# VideoBoy1_12.net
KiCad netlist of a schematic drawn in EAGLE
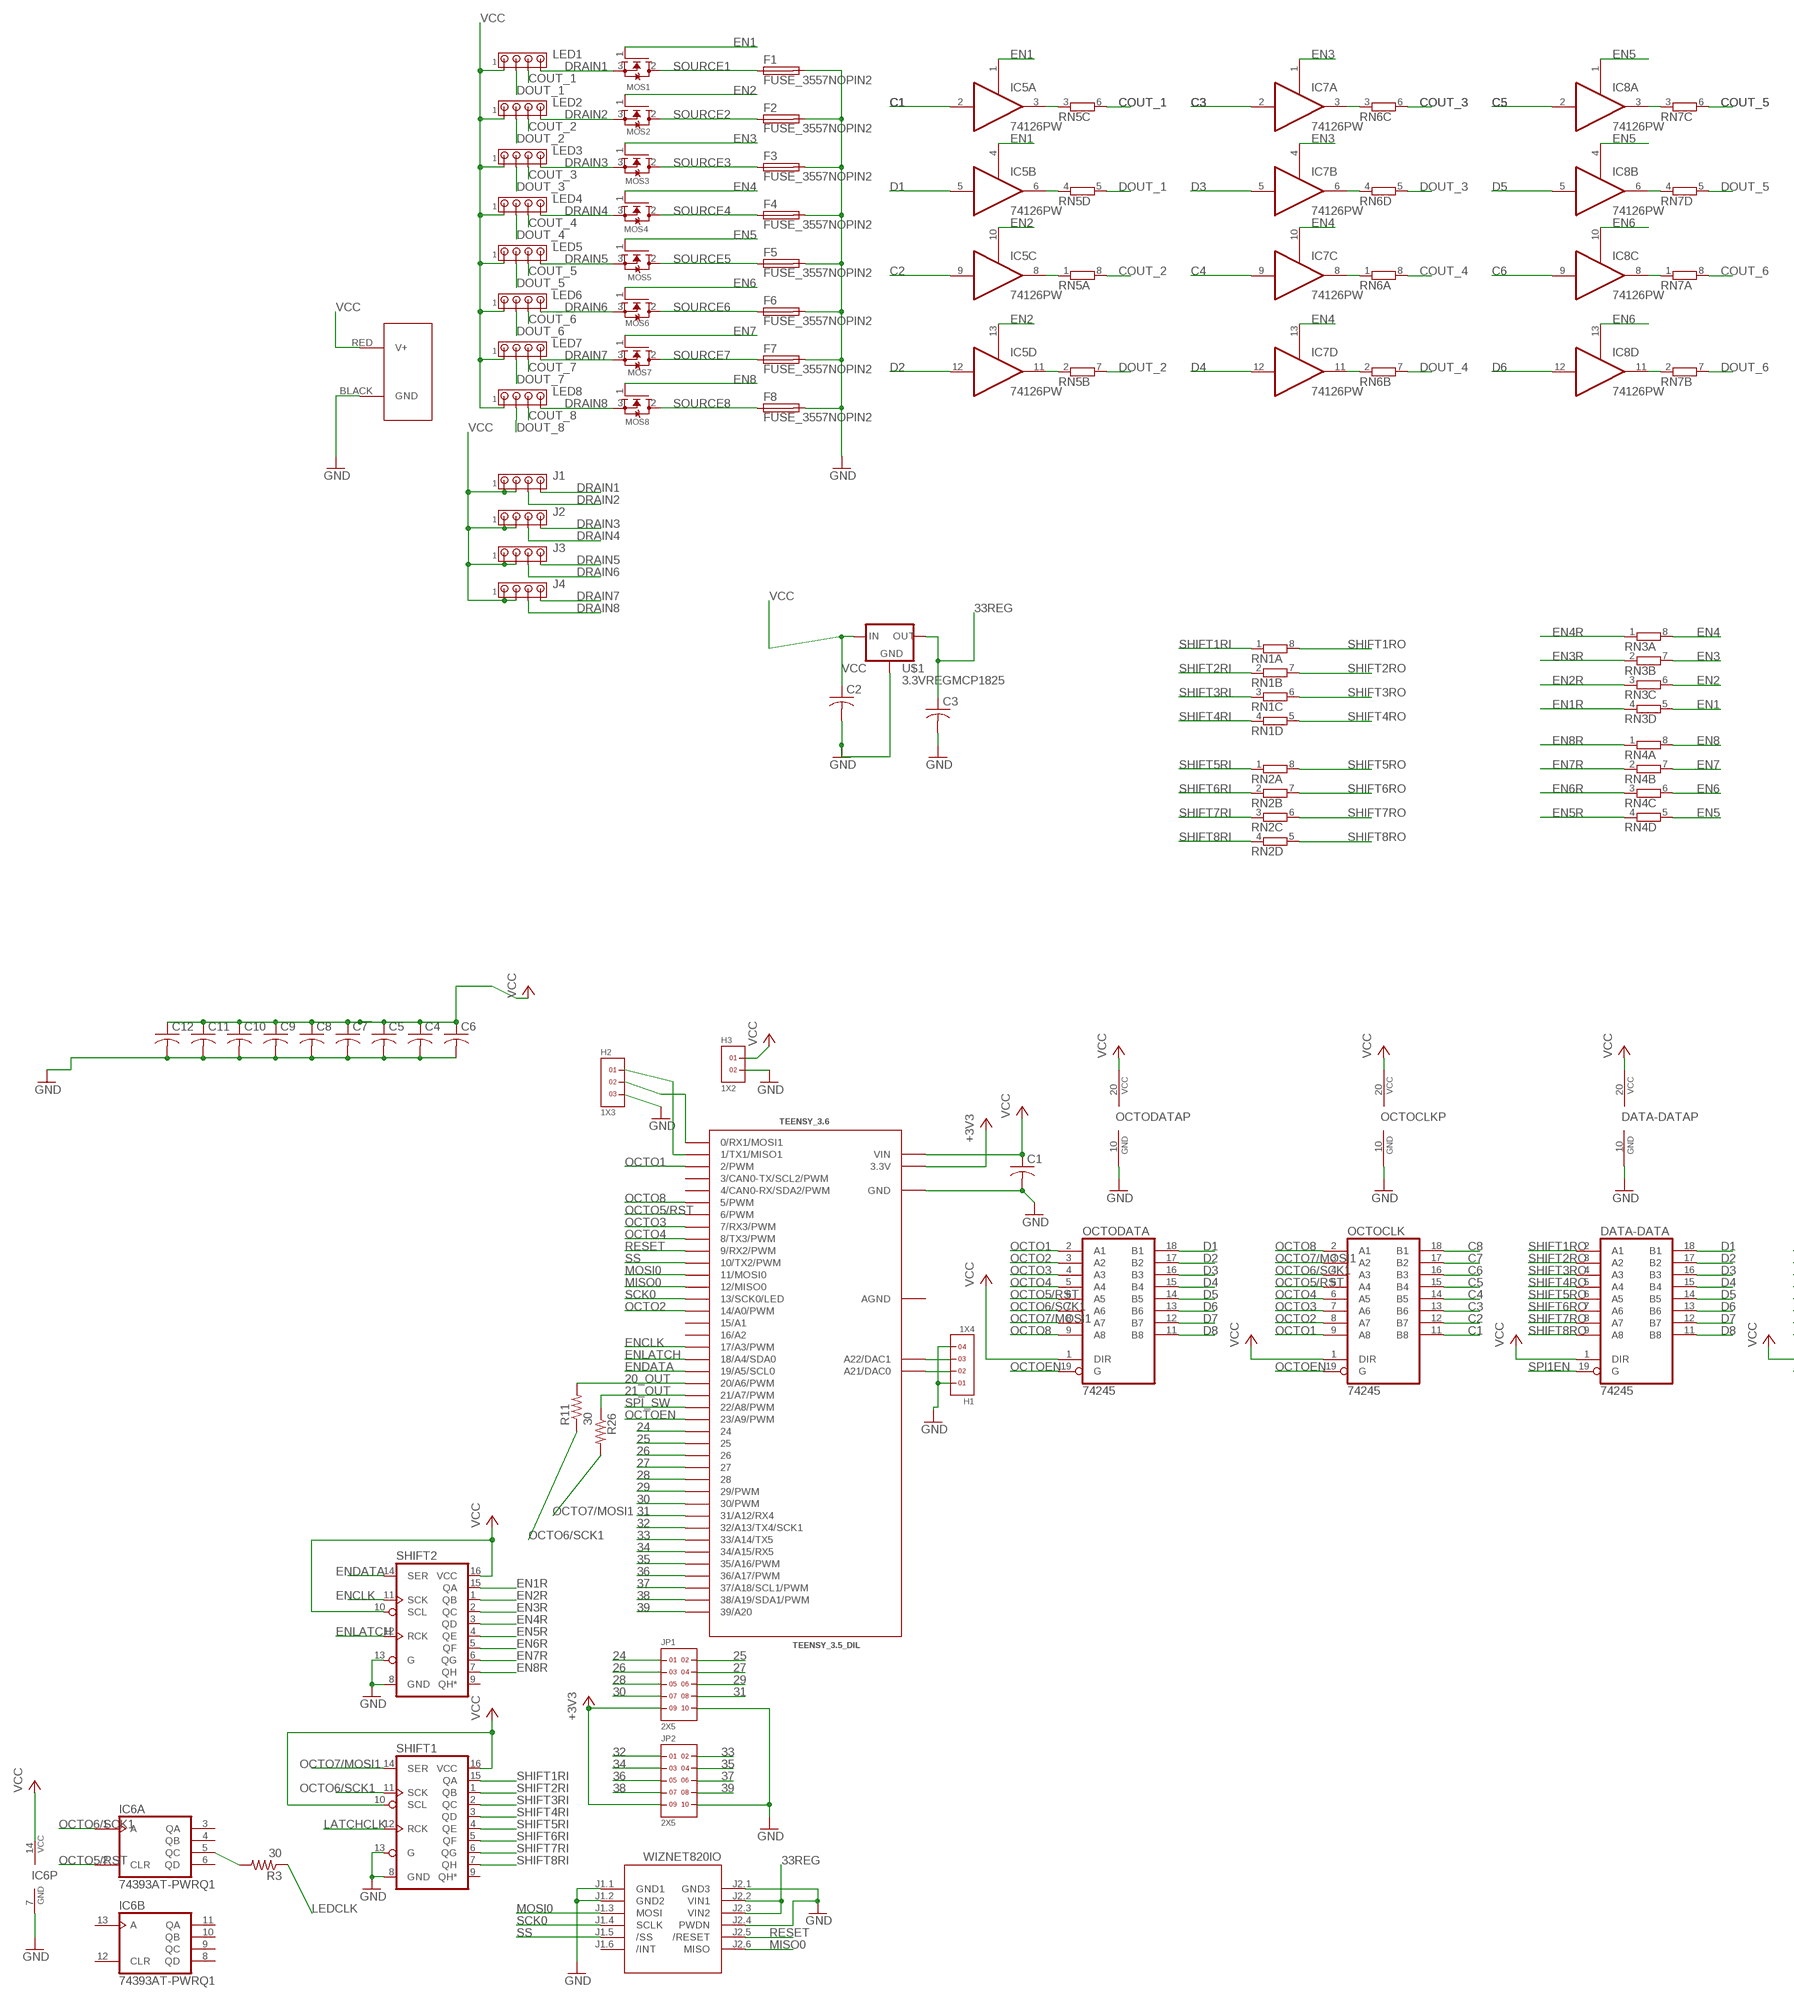
[diagram p0: schematic, sheet 1, part 1 of 2]
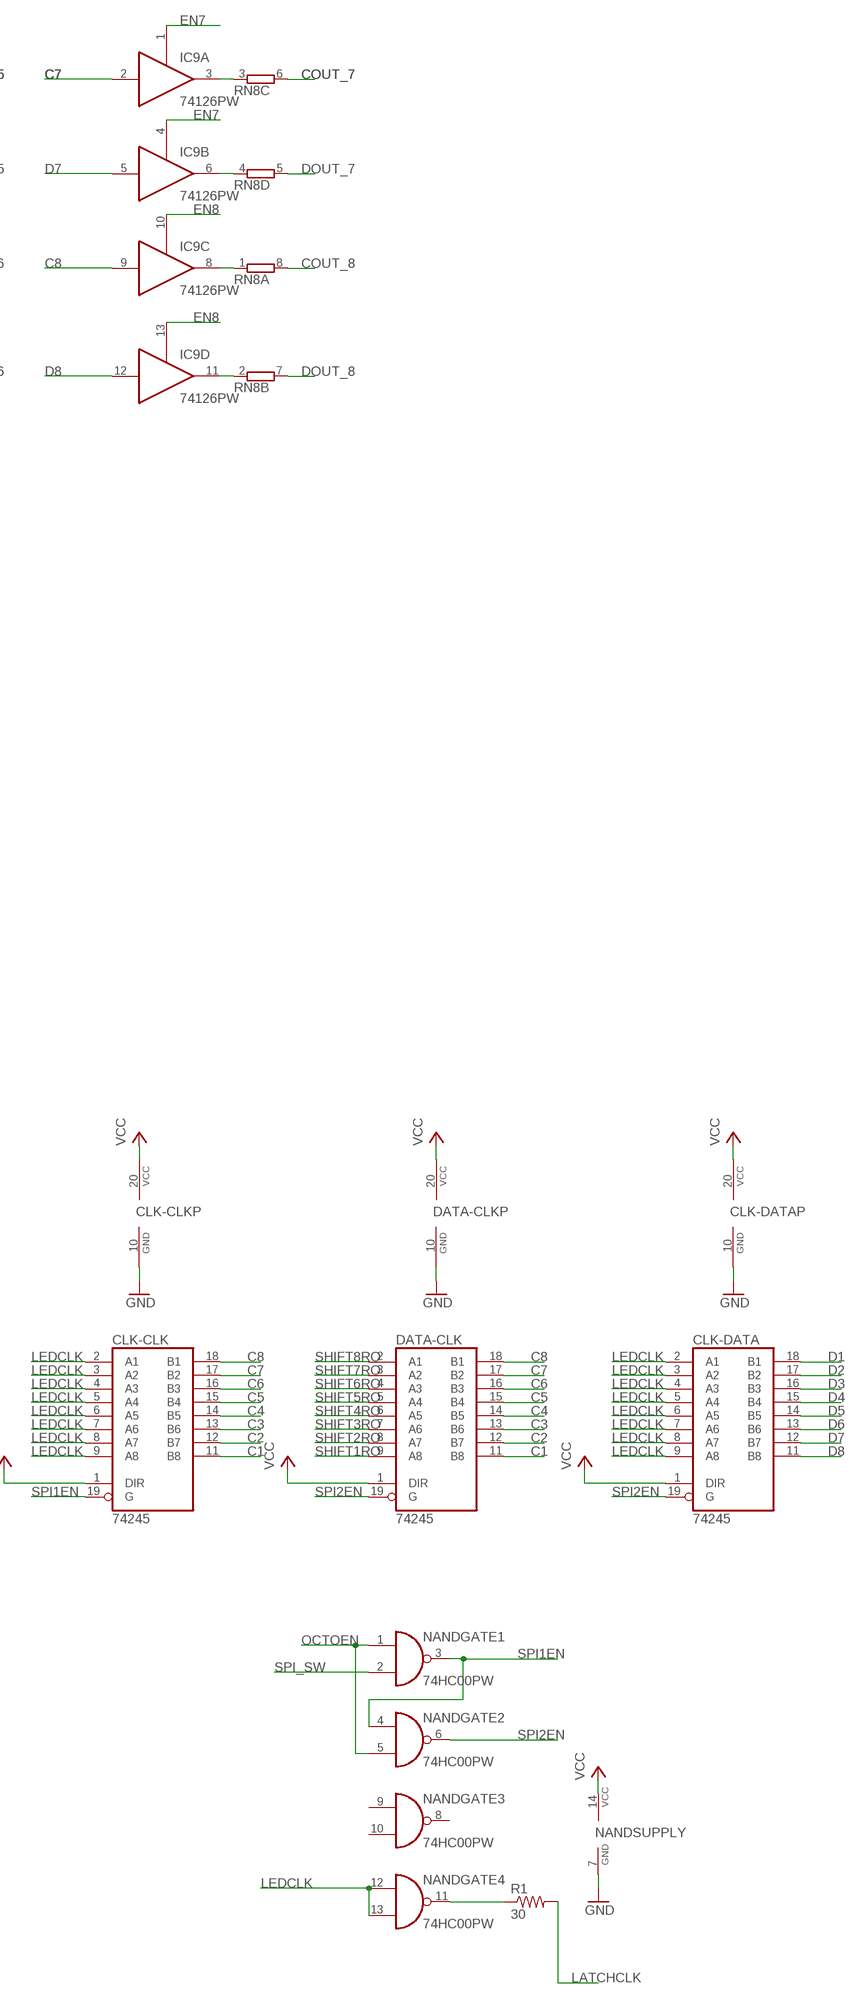
[diagram p1: schematic, sheet 1, part 2 of 2]

(export (version "E")
  (design (tool "Eeschema 10.0.6"))
  (components
    (comp (ref "C1")
      (value "C-USC0603K")
      (footprint "eagle-import:C0603K")
      (libsource (lib "eagle-import") (part "C-USC0603K"))
    )
    (comp (ref "C2")
      (value "C-USC0603K")
      (footprint "eagle-import:C0603K")
      (libsource (lib "eagle-import") (part "C-USC0603K"))
    )
    (comp (ref "C3")
      (value "C-USC0603K")
      (footprint "eagle-import:C0603K")
      (libsource (lib "eagle-import") (part "C-USC0603K"))
    )
    (comp (ref "C4")
      (value "C-USC0603K")
      (footprint "eagle-import:C0603K")
      (libsource (lib "eagle-import") (part "C-USC0603K"))
    )
    (comp (ref "C5")
      (value "C-USC0603K")
      (footprint "eagle-import:C0603K")
      (libsource (lib "eagle-import") (part "C-USC0603K"))
    )
    (comp (ref "C6")
      (value "C-USC0603K")
      (footprint "eagle-import:C0603K")
      (libsource (lib "eagle-import") (part "C-USC0603K"))
    )
    (comp (ref "C7")
      (value "C-USC0603K")
      (footprint "eagle-import:C0603K")
      (libsource (lib "eagle-import") (part "C-USC0603K"))
    )
    (comp (ref "C8")
      (value "C-USC0603K")
      (footprint "eagle-import:C0603K")
      (libsource (lib "eagle-import") (part "C-USC0603K"))
    )
    (comp (ref "C9")
      (value "C-USC0603K")
      (footprint "eagle-import:C0603K")
      (libsource (lib "eagle-import") (part "C-USC0603K"))
    )
    (comp (ref "C10")
      (value "C-USC0603K")
      (footprint "eagle-import:C0603K")
      (libsource (lib "eagle-import") (part "C-USC0603K"))
    )
    (comp (ref "C11")
      (value "C-USC0603K")
      (footprint "eagle-import:C0603K")
      (libsource (lib "eagle-import") (part "C-USC0603K"))
    )
    (comp (ref "C12")
      (value "C-USC0603K")
      (footprint "eagle-import:C0603K")
      (libsource (lib "eagle-import") (part "C-USC0603K"))
    )
    (comp (ref "CLK-CLK")
      (value "74245")
      (footprint "eagle-import:TSSOP20")
      (libsource (lib "eagle-import") (part "74245"))
    )
    (comp (ref "CLK-DATA")
      (value "74245")
      (footprint "eagle-import:TSSOP20")
      (libsource (lib "eagle-import") (part "74245"))
    )
    (comp (ref "DATA-CLK")
      (value "74245")
      (footprint "eagle-import:TSSOP20")
      (libsource (lib "eagle-import") (part "74245"))
    )
    (comp (ref "DATA-DATA")
      (value "74245")
      (footprint "eagle-import:TSSOP20")
      (libsource (lib "eagle-import") (part "74245"))
    )
    (comp (ref "F1")
      (value "FUSE_3557NOPIN2")
      (footprint "eagle-import:3557")
      (libsource (lib "eagle-import") (part "FUSE_3557NOPIN2"))
    )
    (comp (ref "F2")
      (value "FUSE_3557NOPIN2")
      (footprint "eagle-import:3557")
      (libsource (lib "eagle-import") (part "FUSE_3557NOPIN2"))
    )
    (comp (ref "F3")
      (value "FUSE_3557NOPIN2")
      (footprint "eagle-import:3557")
      (libsource (lib "eagle-import") (part "FUSE_3557NOPIN2"))
    )
    (comp (ref "F4")
      (value "FUSE_3557NOPIN2")
      (footprint "eagle-import:3557")
      (libsource (lib "eagle-import") (part "FUSE_3557NOPIN2"))
    )
    (comp (ref "F5")
      (value "FUSE_3557NOPIN2")
      (footprint "eagle-import:3557")
      (libsource (lib "eagle-import") (part "FUSE_3557NOPIN2"))
    )
    (comp (ref "F6")
      (value "FUSE_3557NOPIN2")
      (footprint "eagle-import:3557")
      (libsource (lib "eagle-import") (part "FUSE_3557NOPIN2"))
    )
    (comp (ref "F7")
      (value "FUSE_3557NOPIN2")
      (footprint "eagle-import:3557")
      (libsource (lib "eagle-import") (part "FUSE_3557NOPIN2"))
    )
    (comp (ref "F8")
      (value "FUSE_3557NOPIN2")
      (footprint "eagle-import:3557")
      (libsource (lib "eagle-import") (part "FUSE_3557NOPIN2"))
    )
    (comp (ref "H1")
      (value "1X4")
      (footprint "eagle-import:1X4")
      (libsource (lib "eagle-import") (part "1X4"))
    )
    (comp (ref "H2")
      (value "1X3")
      (footprint "eagle-import:1X3")
      (libsource (lib "eagle-import") (part "1X3"))
    )
    (comp (ref "H3")
      (value "1X2")
      (footprint "eagle-import:1X2")
      (libsource (lib "eagle-import") (part "1X2"))
    )
    (comp (ref "IC5")
      (value "74126PW")
      (footprint "eagle-import:TSSOP14")
      (libsource (lib "eagle-import") (part "74126PW"))
    )
    (comp (ref "IC6")
      (value "74393AT-PWRQ1")
      (footprint "eagle-import:TSSOP14")
      (libsource (lib "eagle-import") (part "74393AT-PWRQ1"))
    )
    (comp (ref "IC7")
      (value "74126PW")
      (footprint "eagle-import:TSSOP14")
      (libsource (lib "eagle-import") (part "74126PW"))
    )
    (comp (ref "IC8")
      (value "74126PW")
      (footprint "eagle-import:TSSOP14")
      (libsource (lib "eagle-import") (part "74126PW"))
    )
    (comp (ref "IC9")
      (value "74126PW")
      (footprint "eagle-import:TSSOP14")
      (libsource (lib "eagle-import") (part "74126PW"))
    )
    (comp (ref "J1")
      (value "4PIN-JST/TE")
      (footprint "eagle-import:BOARDMOUNT-LED")
      (libsource (lib "eagle-import") (part "4PIN-JST/TE"))
    )
    (comp (ref "J2")
      (value "4PIN-JST/TE")
      (footprint "eagle-import:BOARDMOUNT-LED")
      (libsource (lib "eagle-import") (part "4PIN-JST/TE"))
    )
    (comp (ref "J3")
      (value "4PIN-JST/TE")
      (footprint "eagle-import:BOARDMOUNT-LED")
      (libsource (lib "eagle-import") (part "4PIN-JST/TE"))
    )
    (comp (ref "J4")
      (value "4PIN-JST/TE")
      (footprint "eagle-import:BOARDMOUNT-LED")
      (libsource (lib "eagle-import") (part "4PIN-JST/TE"))
    )
    (comp (ref "J5")
      (value "POWERPOLE_POWER25A")
      (footprint "eagle-import:POWERPOLE_PAIR_25A")
      (libsource (lib "eagle-import") (part "POWERPOLE_POWER25A"))
    )
    (comp (ref "JP1")
      (value "2X5")
      (footprint "eagle-import:2X5")
      (libsource (lib "eagle-import") (part "2X5"))
    )
    (comp (ref "JP2")
      (value "2X5")
      (footprint "eagle-import:2X5")
      (libsource (lib "eagle-import") (part "2X5"))
    )
    (comp (ref "LED1")
      (value "4PIN-JST/TE")
      (footprint "eagle-import:BOARDMOUNT-LED")
      (libsource (lib "eagle-import") (part "4PIN-JST/TE"))
    )
    (comp (ref "LED2")
      (value "4PIN-JST/TE")
      (footprint "eagle-import:BOARDMOUNT-LED")
      (libsource (lib "eagle-import") (part "4PIN-JST/TE"))
    )
    (comp (ref "LED3")
      (value "4PIN-JST/TE")
      (footprint "eagle-import:BOARDMOUNT-LED")
      (libsource (lib "eagle-import") (part "4PIN-JST/TE"))
    )
    (comp (ref "LED4")
      (value "4PIN-JST/TE")
      (footprint "eagle-import:BOARDMOUNT-LED")
      (libsource (lib "eagle-import") (part "4PIN-JST/TE"))
    )
    (comp (ref "LED5")
      (value "4PIN-JST/TE")
      (footprint "eagle-import:BOARDMOUNT-LED")
      (libsource (lib "eagle-import") (part "4PIN-JST/TE"))
    )
    (comp (ref "LED6")
      (value "4PIN-JST/TE")
      (footprint "eagle-import:BOARDMOUNT-LED")
      (libsource (lib "eagle-import") (part "4PIN-JST/TE"))
    )
    (comp (ref "LED7")
      (value "4PIN-JST/TE")
      (footprint "eagle-import:BOARDMOUNT-LED")
      (libsource (lib "eagle-import") (part "4PIN-JST/TE"))
    )
    (comp (ref "LED8")
      (value "4PIN-JST/TE")
      (footprint "eagle-import:BOARDMOUNT-LED")
      (libsource (lib "eagle-import") (part "4PIN-JST/TE"))
    )
    (comp (ref "MOS1")
      (value "N-CHANNEL_MOSFET_TO-252")
      (footprint "eagle-import:TO-252")
      (libsource (lib "eagle-import") (part "N-CHANNEL_MOSFET_TO-252"))
    )
    (comp (ref "MOS2")
      (value "N-CHANNEL_MOSFET_TO-252")
      (footprint "eagle-import:TO-252")
      (libsource (lib "eagle-import") (part "N-CHANNEL_MOSFET_TO-252"))
    )
    (comp (ref "MOS3")
      (value "N-CHANNEL_MOSFET_TO-252")
      (footprint "eagle-import:TO-252")
      (libsource (lib "eagle-import") (part "N-CHANNEL_MOSFET_TO-252"))
    )
    (comp (ref "MOS4")
      (value "N-CHANNEL_MOSFET_TO-252")
      (footprint "eagle-import:TO-252")
      (libsource (lib "eagle-import") (part "N-CHANNEL_MOSFET_TO-252"))
    )
    (comp (ref "MOS5")
      (value "N-CHANNEL_MOSFET_TO-252")
      (footprint "eagle-import:TO-252")
      (libsource (lib "eagle-import") (part "N-CHANNEL_MOSFET_TO-252"))
    )
    (comp (ref "MOS6")
      (value "N-CHANNEL_MOSFET_TO-252")
      (footprint "eagle-import:TO-252")
      (libsource (lib "eagle-import") (part "N-CHANNEL_MOSFET_TO-252"))
    )
    (comp (ref "MOS7")
      (value "N-CHANNEL_MOSFET_TO-252")
      (footprint "eagle-import:TO-252")
      (libsource (lib "eagle-import") (part "N-CHANNEL_MOSFET_TO-252"))
    )
    (comp (ref "MOS8")
      (value "N-CHANNEL_MOSFET_TO-252")
      (footprint "eagle-import:TO-252")
      (libsource (lib "eagle-import") (part "N-CHANNEL_MOSFET_TO-252"))
    )
    (comp (ref "NAND")
      (value "74HC00PW")
      (footprint "eagle-import:TSSOP14")
      (libsource (lib "eagle-import") (part "74HC00PW"))
    )
    (comp (ref "OCTOCLK")
      (value "74245")
      (footprint "eagle-import:TSSOP20")
      (libsource (lib "eagle-import") (part "74245"))
    )
    (comp (ref "OCTODATA")
      (value "74245")
      (footprint "eagle-import:TSSOP20")
      (libsource (lib "eagle-import") (part "74245"))
    )
    (comp (ref "R1")
      (value "30")
      (footprint "eagle-import:R0603")
      (libsource (lib "eagle-import") (part "R-US_R0603"))
    )
    (comp (ref "R3")
      (value "30")
      (footprint "eagle-import:R0603")
      (libsource (lib "eagle-import") (part "R-US_R0603"))
    )
    (comp (ref "R11")
      (value "30")
      (footprint "eagle-import:R0603")
      (libsource (lib "eagle-import") (part "R-US_R0603"))
    )
    (comp (ref "R26")
      (value "R-US_R0603")
      (footprint "eagle-import:R0603")
      (libsource (lib "eagle-import") (part "R-US_R0603"))
    )
    (comp (ref "RN1")
      (value "4R-N0603-ARV")
      (footprint "eagle-import:0603-ARV")
      (libsource (lib "eagle-import") (part "4R-N0603-ARV"))
    )
    (comp (ref "RN2")
      (value "4R-N0603-ARV")
      (footprint "eagle-import:0603-ARV")
      (libsource (lib "eagle-import") (part "4R-N0603-ARV"))
    )
    (comp (ref "RN3")
      (value "4R-N0603-ARV")
      (footprint "eagle-import:0603-ARV")
      (libsource (lib "eagle-import") (part "4R-N0603-ARV"))
    )
    (comp (ref "RN4")
      (value "4R-N0603-ARV")
      (footprint "eagle-import:0603-ARV")
      (libsource (lib "eagle-import") (part "4R-N0603-ARV"))
    )
    (comp (ref "RN5")
      (value "4R-N0603-ARV")
      (footprint "eagle-import:0603-ARV")
      (libsource (lib "eagle-import") (part "4R-N0603-ARV"))
    )
    (comp (ref "RN6")
      (value "4R-N0603-ARV")
      (footprint "eagle-import:0603-ARV")
      (libsource (lib "eagle-import") (part "4R-N0603-ARV"))
    )
    (comp (ref "RN7")
      (value "4R-N0603-ARV")
      (footprint "eagle-import:0603-ARV")
      (libsource (lib "eagle-import") (part "4R-N0603-ARV"))
    )
    (comp (ref "RN8")
      (value "4R-N0603-ARV")
      (footprint "eagle-import:0603-ARV")
      (libsource (lib "eagle-import") (part "4R-N0603-ARV"))
    )
    (comp (ref "SHIFT1")
      (value "74595PWR")
      (footprint "eagle-import:TSSOP16")
      (libsource (lib "eagle-import") (part "74595PWR"))
    )
    (comp (ref "SHIFT2")
      (value "74595PWR")
      (footprint "eagle-import:TSSOP16")
      (libsource (lib "eagle-import") (part "74595PWR"))
    )
    (comp (ref "TEENSY_3.6")
      (value "TEENSY_3.5_DIL")
      (footprint "eagle-import:TEENSY_3.5_DIL")
      (libsource (lib "eagle-import") (part "TEENSY_3.5_DIL"))
    )
    (comp (ref "U$1")
      (value "3.3VREGMCP1825")
      (footprint "eagle-import:SOT223")
      (libsource (lib "eagle-import") (part "3.3VREGMCP1825"))
    )
    (comp (ref "WIZNET820IO")
      (value "WIZ820IO_DEVICE'DUAL-IN-LINE'")
      (footprint "eagle-import:WIZ820IO")
      (libsource (lib "eagle-import") (part "WIZ820IO_DEVICE'DUAL-IN-LINE'"))
    )
  )
  (nets
    (net (code "1") (name "+3V3") (class "Default")
      (node (ref "JP1") (pin "9") (pinfunction "9_9") (pintype "bidirectional"))
      (node (ref "JP2") (pin "9") (pinfunction "9_9") (pintype "bidirectional"))
      (node (ref "TEENSY_3.6") (pin "3.3V") (pinfunction "3.3V_3.3V") (pintype "power_in"))
      (node (ref "TEENSY_3.6") (pin "3.3V3") (pinfunction "3.3V_3.3V3") (pintype "power_in"))
    )
    (net (code "2") (name "/20_OUT") (class "Default")
      (node (ref "R11") (pin "2") (pinfunction "2_2") (pintype "passive"))
      (node (ref "TEENSY_3.6") (pin "20/A6") (pinfunction "20/A6/PWM_20/A6") (pintype "bidirectional"))
    )
    (net (code "3") (name "/21_OUT") (class "Default")
      (node (ref "R26") (pin "1") (pinfunction "1_1") (pintype "passive"))
      (node (ref "TEENSY_3.6") (pin "21/A7") (pinfunction "21/A7/PWM_21/A7") (pintype "bidirectional"))
    )
    (net (code "4") (name "/24") (class "Default")
      (node (ref "JP1") (pin "1") (pinfunction "1_1") (pintype "bidirectional"))
      (node (ref "TEENSY_3.6") (pin "24") (pinfunction "24_24") (pintype "bidirectional"))
    )
    (net (code "5") (name "/25") (class "Default")
      (node (ref "JP1") (pin "2") (pinfunction "2_2") (pintype "bidirectional"))
      (node (ref "TEENSY_3.6") (pin "25") (pinfunction "25_25") (pintype "bidirectional"))
    )
    (net (code "6") (name "/26") (class "Default")
      (node (ref "JP1") (pin "3") (pinfunction "3_3") (pintype "bidirectional"))
      (node (ref "TEENSY_3.6") (pin "26") (pinfunction "26_26") (pintype "bidirectional"))
    )
    (net (code "7") (name "/27") (class "Default")
      (node (ref "JP1") (pin "4") (pinfunction "4_4") (pintype "bidirectional"))
      (node (ref "TEENSY_3.6") (pin "27") (pinfunction "27_27") (pintype "bidirectional"))
    )
    (net (code "8") (name "/28") (class "Default")
      (node (ref "JP1") (pin "5") (pinfunction "5_5") (pintype "bidirectional"))
      (node (ref "TEENSY_3.6") (pin "28") (pinfunction "28_28") (pintype "bidirectional"))
    )
    (net (code "9") (name "/29") (class "Default")
      (node (ref "JP1") (pin "6") (pinfunction "6_6") (pintype "bidirectional"))
      (node (ref "TEENSY_3.6") (pin "29") (pinfunction "29/PWM_29") (pintype "bidirectional"))
    )
    (net (code "10") (name "/30") (class "Default")
      (node (ref "JP1") (pin "7") (pinfunction "7_7") (pintype "bidirectional"))
      (node (ref "TEENSY_3.6") (pin "30") (pinfunction "30/PWM_30") (pintype "bidirectional"))
    )
    (net (code "11") (name "/31") (class "Default")
      (node (ref "JP1") (pin "8") (pinfunction "8_8") (pintype "bidirectional"))
      (node (ref "TEENSY_3.6") (pin "31/A12") (pinfunction "31/A12/RX4_31/A12") (pintype "bidirectional"))
    )
    (net (code "12") (name "/32") (class "Default")
      (node (ref "JP2") (pin "1") (pinfunction "1_1") (pintype "bidirectional"))
      (node (ref "TEENSY_3.6") (pin "32/A13") (pinfunction "32/A13/TX4/SCK1_32/A13") (pintype "bidirectional"))
    )
    (net (code "13") (name "/33") (class "Default")
      (node (ref "JP2") (pin "2") (pinfunction "2_2") (pintype "bidirectional"))
      (node (ref "TEENSY_3.6") (pin "33/A14") (pinfunction "33/A14/TX5_33/A14") (pintype "bidirectional"))
    )
    (net (code "14") (name "/33REG") (class "Default")
      (node (ref "C3") (pin "1") (pinfunction "1_1") (pintype "passive"))
      (node (ref "U$1") (pin "3") (pinfunction "OUT_3") (pintype "passive"))
      (node (ref "WIZNET820IO") (pin "J2.2") (pinfunction "VIN1_J2.2") (pintype "power_in"))
      (node (ref "WIZNET820IO") (pin "J2.3") (pinfunction "VIN2_J2.3") (pintype "power_in"))
    )
    (net (code "15") (name "/34") (class "Default")
      (node (ref "JP2") (pin "3") (pinfunction "3_3") (pintype "bidirectional"))
      (node (ref "TEENSY_3.6") (pin "34/A15") (pinfunction "34/A15/RX5_34/A15") (pintype "bidirectional"))
    )
    (net (code "16") (name "/35") (class "Default")
      (node (ref "JP2") (pin "4") (pinfunction "4_4") (pintype "bidirectional"))
      (node (ref "TEENSY_3.6") (pin "35/A16") (pinfunction "35/A16/PWM_35/A16") (pintype "bidirectional"))
    )
    (net (code "17") (name "/36") (class "Default")
      (node (ref "JP2") (pin "5") (pinfunction "5_5") (pintype "bidirectional"))
      (node (ref "TEENSY_3.6") (pin "36/A17") (pinfunction "36/A17/PWM_36/A17") (pintype "bidirectional"))
    )
    (net (code "18") (name "/37") (class "Default")
      (node (ref "JP2") (pin "6") (pinfunction "6_6") (pintype "bidirectional"))
      (node (ref "TEENSY_3.6") (pin "37/A18") (pinfunction "37/A18/SCL1/PWM_37/A18") (pintype "bidirectional"))
    )
    (net (code "19") (name "/38") (class "Default")
      (node (ref "JP2") (pin "7") (pinfunction "7_7") (pintype "bidirectional"))
      (node (ref "TEENSY_3.6") (pin "38/A19") (pinfunction "38/A19/SDA1/PWM_38/A19") (pintype "bidirectional"))
    )
    (net (code "20") (name "/39") (class "Default")
      (node (ref "JP2") (pin "8") (pinfunction "8_8") (pintype "bidirectional"))
      (node (ref "TEENSY_3.6") (pin "39/A20") (pinfunction "39/A20_39/A20") (pintype "bidirectional"))
    )
    (net (code "21") (name "/AGND") (class "Default")
      (node (ref "TEENSY_3.6") (pin "AGND") (pinfunction "AGND_AGND") (pintype "power_in"))
    )
    (net (code "22") (name "/C1") (class "Default")
      (node (ref "CLK-CLK") (pin "11") (pinfunction "B8_11") (pintype "bidirectional"))
      (node (ref "DATA-CLK") (pin "11") (pinfunction "B8_11") (pintype "bidirectional"))
      (node (ref "IC5") (pin "2") (pinfunction "I_2") (pintype "input"))
      (node (ref "OCTOCLK") (pin "11") (pinfunction "B8_11") (pintype "bidirectional"))
    )
    (net (code "23") (name "/C2") (class "Default")
      (node (ref "CLK-CLK") (pin "12") (pinfunction "B7_12") (pintype "bidirectional"))
      (node (ref "DATA-CLK") (pin "12") (pinfunction "B7_12") (pintype "bidirectional"))
      (node (ref "IC5") (pin "9") (pinfunction "I_9") (pintype "input"))
      (node (ref "OCTOCLK") (pin "12") (pinfunction "B7_12") (pintype "bidirectional"))
    )
    (net (code "24") (name "/C3") (class "Default")
      (node (ref "CLK-CLK") (pin "13") (pinfunction "B6_13") (pintype "bidirectional"))
      (node (ref "DATA-CLK") (pin "13") (pinfunction "B6_13") (pintype "bidirectional"))
      (node (ref "IC7") (pin "2") (pinfunction "I_2") (pintype "input"))
      (node (ref "OCTOCLK") (pin "13") (pinfunction "B6_13") (pintype "bidirectional"))
    )
    (net (code "25") (name "/C4") (class "Default")
      (node (ref "CLK-CLK") (pin "14") (pinfunction "B5_14") (pintype "bidirectional"))
      (node (ref "DATA-CLK") (pin "14") (pinfunction "B5_14") (pintype "bidirectional"))
      (node (ref "IC7") (pin "9") (pinfunction "I_9") (pintype "input"))
      (node (ref "OCTOCLK") (pin "14") (pinfunction "B5_14") (pintype "bidirectional"))
    )
    (net (code "26") (name "/C5") (class "Default")
      (node (ref "CLK-CLK") (pin "15") (pinfunction "B4_15") (pintype "bidirectional"))
      (node (ref "DATA-CLK") (pin "15") (pinfunction "B4_15") (pintype "bidirectional"))
      (node (ref "IC8") (pin "2") (pinfunction "I_2") (pintype "input"))
      (node (ref "OCTOCLK") (pin "15") (pinfunction "B4_15") (pintype "bidirectional"))
    )
    (net (code "27") (name "/C6") (class "Default")
      (node (ref "CLK-CLK") (pin "16") (pinfunction "B3_16") (pintype "bidirectional"))
      (node (ref "DATA-CLK") (pin "16") (pinfunction "B3_16") (pintype "bidirectional"))
      (node (ref "IC8") (pin "9") (pinfunction "I_9") (pintype "input"))
      (node (ref "OCTOCLK") (pin "16") (pinfunction "B3_16") (pintype "bidirectional"))
    )
    (net (code "28") (name "/C7") (class "Default")
      (node (ref "CLK-CLK") (pin "17") (pinfunction "B2_17") (pintype "bidirectional"))
      (node (ref "DATA-CLK") (pin "17") (pinfunction "B2_17") (pintype "bidirectional"))
      (node (ref "IC9") (pin "2") (pinfunction "I_2") (pintype "input"))
      (node (ref "OCTOCLK") (pin "17") (pinfunction "B2_17") (pintype "bidirectional"))
    )
    (net (code "29") (name "/C8") (class "Default")
      (node (ref "CLK-CLK") (pin "18") (pinfunction "B1_18") (pintype "bidirectional"))
      (node (ref "DATA-CLK") (pin "18") (pinfunction "B1_18") (pintype "bidirectional"))
      (node (ref "IC9") (pin "9") (pinfunction "I_9") (pintype "input"))
      (node (ref "OCTOCLK") (pin "18") (pinfunction "B1_18") (pintype "bidirectional"))
    )
    (net (code "30") (name "/COUT_1") (class "Default")
      (node (ref "LED1") (pin "3") (pinfunction "3_3") (pintype "passive"))
      (node (ref "RN5") (pin "6") (pinfunction "2_6") (pintype "passive"))
    )
    (net (code "31") (name "/COUT_2") (class "Default")
      (node (ref "LED2") (pin "3") (pinfunction "3_3") (pintype "passive"))
      (node (ref "RN5") (pin "8") (pinfunction "2_8") (pintype "passive"))
    )
    (net (code "32") (name "/COUT_3") (class "Default")
      (node (ref "LED3") (pin "3") (pinfunction "3_3") (pintype "passive"))
      (node (ref "RN6") (pin "6") (pinfunction "2_6") (pintype "passive"))
    )
    (net (code "33") (name "/COUT_4") (class "Default")
      (node (ref "LED4") (pin "3") (pinfunction "3_3") (pintype "passive"))
      (node (ref "RN6") (pin "8") (pinfunction "2_8") (pintype "passive"))
    )
    (net (code "34") (name "/COUT_5") (class "Default")
      (node (ref "LED5") (pin "3") (pinfunction "3_3") (pintype "passive"))
      (node (ref "RN7") (pin "6") (pinfunction "2_6") (pintype "passive"))
    )
    (net (code "35") (name "/COUT_6") (class "Default")
      (node (ref "LED6") (pin "3") (pinfunction "3_3") (pintype "passive"))
      (node (ref "RN7") (pin "8") (pinfunction "2_8") (pintype "passive"))
    )
    (net (code "36") (name "/COUT_7") (class "Default")
      (node (ref "LED7") (pin "3") (pinfunction "3_3") (pintype "passive"))
      (node (ref "RN8") (pin "6") (pinfunction "2_6") (pintype "passive"))
    )
    (net (code "37") (name "/COUT_8") (class "Default")
      (node (ref "LED8") (pin "3") (pinfunction "3_3") (pintype "passive"))
      (node (ref "RN8") (pin "8") (pinfunction "2_8") (pintype "passive"))
    )
    (net (code "38") (name "/D1") (class "Default")
      (node (ref "CLK-DATA") (pin "18") (pinfunction "B1_18") (pintype "bidirectional"))
      (node (ref "DATA-DATA") (pin "18") (pinfunction "B1_18") (pintype "bidirectional"))
      (node (ref "IC5") (pin "5") (pinfunction "I_5") (pintype "input"))
      (node (ref "OCTODATA") (pin "18") (pinfunction "B1_18") (pintype "bidirectional"))
    )
    (net (code "39") (name "/D2") (class "Default")
      (node (ref "CLK-DATA") (pin "17") (pinfunction "B2_17") (pintype "bidirectional"))
      (node (ref "DATA-DATA") (pin "17") (pinfunction "B2_17") (pintype "bidirectional"))
      (node (ref "IC5") (pin "12") (pinfunction "I_12") (pintype "input"))
      (node (ref "OCTODATA") (pin "17") (pinfunction "B2_17") (pintype "bidirectional"))
    )
    (net (code "40") (name "/D3") (class "Default")
      (node (ref "CLK-DATA") (pin "16") (pinfunction "B3_16") (pintype "bidirectional"))
      (node (ref "DATA-DATA") (pin "16") (pinfunction "B3_16") (pintype "bidirectional"))
      (node (ref "IC7") (pin "5") (pinfunction "I_5") (pintype "input"))
      (node (ref "OCTODATA") (pin "16") (pinfunction "B3_16") (pintype "bidirectional"))
    )
    (net (code "41") (name "/D4") (class "Default")
      (node (ref "CLK-DATA") (pin "15") (pinfunction "B4_15") (pintype "bidirectional"))
      (node (ref "DATA-DATA") (pin "15") (pinfunction "B4_15") (pintype "bidirectional"))
      (node (ref "IC7") (pin "12") (pinfunction "I_12") (pintype "input"))
      (node (ref "OCTODATA") (pin "15") (pinfunction "B4_15") (pintype "bidirectional"))
    )
    (net (code "42") (name "/D5") (class "Default")
      (node (ref "CLK-DATA") (pin "14") (pinfunction "B5_14") (pintype "bidirectional"))
      (node (ref "DATA-DATA") (pin "14") (pinfunction "B5_14") (pintype "bidirectional"))
      (node (ref "IC8") (pin "5") (pinfunction "I_5") (pintype "input"))
      (node (ref "OCTODATA") (pin "14") (pinfunction "B5_14") (pintype "bidirectional"))
    )
    (net (code "43") (name "/D6") (class "Default")
      (node (ref "CLK-DATA") (pin "13") (pinfunction "B6_13") (pintype "bidirectional"))
      (node (ref "DATA-DATA") (pin "13") (pinfunction "B6_13") (pintype "bidirectional"))
      (node (ref "IC8") (pin "12") (pinfunction "I_12") (pintype "input"))
      (node (ref "OCTODATA") (pin "13") (pinfunction "B6_13") (pintype "bidirectional"))
    )
    (net (code "44") (name "/D7") (class "Default")
      (node (ref "CLK-DATA") (pin "12") (pinfunction "B7_12") (pintype "bidirectional"))
      (node (ref "DATA-DATA") (pin "12") (pinfunction "B7_12") (pintype "bidirectional"))
      (node (ref "IC9") (pin "5") (pinfunction "I_5") (pintype "input"))
      (node (ref "OCTODATA") (pin "12") (pinfunction "B7_12") (pintype "bidirectional"))
    )
    (net (code "45") (name "/D8") (class "Default")
      (node (ref "CLK-DATA") (pin "11") (pinfunction "B8_11") (pintype "bidirectional"))
      (node (ref "DATA-DATA") (pin "11") (pinfunction "B8_11") (pintype "bidirectional"))
      (node (ref "IC9") (pin "12") (pinfunction "I_12") (pintype "input"))
      (node (ref "OCTODATA") (pin "11") (pinfunction "B8_11") (pintype "bidirectional"))
    )
    (net (code "46") (name "/DOUT_1") (class "Default")
      (node (ref "LED1") (pin "2") (pinfunction "2_2") (pintype "passive"))
      (node (ref "RN5") (pin "5") (pinfunction "2_5") (pintype "passive"))
    )
    (net (code "47") (name "/DOUT_2") (class "Default")
      (node (ref "LED2") (pin "2") (pinfunction "2_2") (pintype "passive"))
      (node (ref "RN5") (pin "7") (pinfunction "2_7") (pintype "passive"))
    )
    (net (code "48") (name "/DOUT_3") (class "Default")
      (node (ref "LED3") (pin "2") (pinfunction "2_2") (pintype "passive"))
      (node (ref "RN6") (pin "5") (pinfunction "2_5") (pintype "passive"))
    )
    (net (code "49") (name "/DOUT_4") (class "Default")
      (node (ref "LED4") (pin "2") (pinfunction "2_2") (pintype "passive"))
      (node (ref "RN6") (pin "7") (pinfunction "2_7") (pintype "passive"))
    )
    (net (code "50") (name "/DOUT_5") (class "Default")
      (node (ref "LED5") (pin "2") (pinfunction "2_2") (pintype "passive"))
      (node (ref "RN7") (pin "5") (pinfunction "2_5") (pintype "passive"))
    )
    (net (code "51") (name "/DOUT_6") (class "Default")
      (node (ref "LED6") (pin "2") (pinfunction "2_2") (pintype "passive"))
      (node (ref "RN7") (pin "7") (pinfunction "2_7") (pintype "passive"))
    )
    (net (code "52") (name "/DOUT_7") (class "Default")
      (node (ref "LED7") (pin "2") (pinfunction "2_2") (pintype "passive"))
      (node (ref "RN8") (pin "5") (pinfunction "2_5") (pintype "passive"))
    )
    (net (code "53") (name "/DOUT_8") (class "Default")
      (node (ref "LED8") (pin "2") (pinfunction "2_2") (pintype "passive"))
      (node (ref "RN8") (pin "7") (pinfunction "2_7") (pintype "passive"))
    )
    (net (code "54") (name "/DRAIN1") (class "Default")
      (node (ref "J1") (pin "4") (pinfunction "4_4") (pintype "passive"))
      (node (ref "LED1") (pin "4") (pinfunction "4_4") (pintype "passive"))
      (node (ref "MOS1") (pin "3") (pinfunction "S_3") (pintype "bidirectional"))
    )
    (net (code "55") (name "/DRAIN2") (class "Default")
      (node (ref "J1") (pin "3") (pinfunction "3_3") (pintype "passive"))
      (node (ref "LED2") (pin "4") (pinfunction "4_4") (pintype "passive"))
      (node (ref "MOS2") (pin "3") (pinfunction "S_3") (pintype "bidirectional"))
    )
    (net (code "56") (name "/DRAIN3") (class "Default")
      (node (ref "J2") (pin "4") (pinfunction "4_4") (pintype "passive"))
      (node (ref "LED3") (pin "4") (pinfunction "4_4") (pintype "passive"))
      (node (ref "MOS3") (pin "3") (pinfunction "S_3") (pintype "bidirectional"))
    )
    (net (code "57") (name "/DRAIN4") (class "Default")
      (node (ref "J2") (pin "3") (pinfunction "3_3") (pintype "passive"))
      (node (ref "LED4") (pin "4") (pinfunction "4_4") (pintype "passive"))
      (node (ref "MOS4") (pin "3") (pinfunction "S_3") (pintype "bidirectional"))
    )
    (net (code "58") (name "/DRAIN5") (class "Default")
      (node (ref "J3") (pin "4") (pinfunction "4_4") (pintype "passive"))
      (node (ref "LED5") (pin "4") (pinfunction "4_4") (pintype "passive"))
      (node (ref "MOS5") (pin "3") (pinfunction "S_3") (pintype "bidirectional"))
    )
    (net (code "59") (name "/DRAIN6") (class "Default")
      (node (ref "J3") (pin "3") (pinfunction "3_3") (pintype "passive"))
      (node (ref "LED6") (pin "4") (pinfunction "4_4") (pintype "passive"))
      (node (ref "MOS6") (pin "3") (pinfunction "S_3") (pintype "bidirectional"))
    )
    (net (code "60") (name "/DRAIN7") (class "Default")
      (node (ref "J4") (pin "4") (pinfunction "4_4") (pintype "passive"))
      (node (ref "LED7") (pin "4") (pinfunction "4_4") (pintype "passive"))
      (node (ref "MOS7") (pin "3") (pinfunction "S_3") (pintype "bidirectional"))
    )
    (net (code "61") (name "/DRAIN8") (class "Default")
      (node (ref "J4") (pin "3") (pinfunction "3_3") (pintype "passive"))
      (node (ref "LED8") (pin "4") (pinfunction "4_4") (pintype "passive"))
      (node (ref "MOS8") (pin "3") (pinfunction "S_3") (pintype "bidirectional"))
    )
    (net (code "62") (name "/EN1") (class "Default")
      (node (ref "IC5") (pin "1") (pinfunction "OE_1") (pintype "input"))
      (node (ref "IC5") (pin "4") (pinfunction "OE_4") (pintype "input"))
      (node (ref "MOS1") (pin "1") (pinfunction "G_1") (pintype "bidirectional"))
      (node (ref "RN3") (pin "5") (pinfunction "2_5") (pintype "passive"))
    )
    (net (code "63") (name "/EN1R") (class "Default")
      (node (ref "RN3") (pin "4") (pinfunction "1_4") (pintype "passive"))
      (node (ref "SHIFT2") (pin "15") (pinfunction "QA_15") (pintype "tri_state"))
    )
    (net (code "64") (name "/EN2") (class "Default")
      (node (ref "IC5") (pin "10") (pinfunction "OE_10") (pintype "input"))
      (node (ref "IC5") (pin "13") (pinfunction "OE_13") (pintype "input"))
      (node (ref "MOS2") (pin "1") (pinfunction "G_1") (pintype "bidirectional"))
      (node (ref "RN3") (pin "6") (pinfunction "2_6") (pintype "passive"))
    )
    (net (code "65") (name "/EN2R") (class "Default")
      (node (ref "RN3") (pin "3") (pinfunction "1_3") (pintype "passive"))
      (node (ref "SHIFT2") (pin "1") (pinfunction "QB_1") (pintype "tri_state"))
    )
    (net (code "66") (name "/EN3") (class "Default")
      (node (ref "IC7") (pin "1") (pinfunction "OE_1") (pintype "input"))
      (node (ref "IC7") (pin "4") (pinfunction "OE_4") (pintype "input"))
      (node (ref "MOS3") (pin "1") (pinfunction "G_1") (pintype "bidirectional"))
      (node (ref "RN3") (pin "7") (pinfunction "2_7") (pintype "passive"))
    )
    (net (code "67") (name "/EN3R") (class "Default")
      (node (ref "RN3") (pin "2") (pinfunction "1_2") (pintype "passive"))
      (node (ref "SHIFT2") (pin "2") (pinfunction "QC_2") (pintype "tri_state"))
    )
    (net (code "68") (name "/EN4") (class "Default")
      (node (ref "IC7") (pin "10") (pinfunction "OE_10") (pintype "input"))
      (node (ref "IC7") (pin "13") (pinfunction "OE_13") (pintype "input"))
      (node (ref "MOS4") (pin "1") (pinfunction "G_1") (pintype "bidirectional"))
      (node (ref "RN3") (pin "8") (pinfunction "2_8") (pintype "passive"))
    )
    (net (code "69") (name "/EN4R") (class "Default")
      (node (ref "RN3") (pin "1") (pinfunction "1_1") (pintype "passive"))
      (node (ref "SHIFT2") (pin "3") (pinfunction "QD_3") (pintype "tri_state"))
    )
    (net (code "70") (name "/EN5") (class "Default")
      (node (ref "IC8") (pin "1") (pinfunction "OE_1") (pintype "input"))
      (node (ref "IC8") (pin "4") (pinfunction "OE_4") (pintype "input"))
      (node (ref "MOS5") (pin "1") (pinfunction "G_1") (pintype "bidirectional"))
      (node (ref "RN4") (pin "5") (pinfunction "2_5") (pintype "passive"))
    )
    (net (code "71") (name "/EN5R") (class "Default")
      (node (ref "RN4") (pin "4") (pinfunction "1_4") (pintype "passive"))
      (node (ref "SHIFT2") (pin "4") (pinfunction "QE_4") (pintype "tri_state"))
    )
    (net (code "72") (name "/EN6") (class "Default")
      (node (ref "IC8") (pin "10") (pinfunction "OE_10") (pintype "input"))
      (node (ref "IC8") (pin "13") (pinfunction "OE_13") (pintype "input"))
      (node (ref "MOS6") (pin "1") (pinfunction "G_1") (pintype "bidirectional"))
      (node (ref "RN4") (pin "6") (pinfunction "2_6") (pintype "passive"))
    )
    (net (code "73") (name "/EN6R") (class "Default")
      (node (ref "RN4") (pin "3") (pinfunction "1_3") (pintype "passive"))
      (node (ref "SHIFT2") (pin "5") (pinfunction "QF_5") (pintype "tri_state"))
    )
    (net (code "74") (name "/EN7") (class "Default")
      (node (ref "IC9") (pin "1") (pinfunction "OE_1") (pintype "input"))
      (node (ref "IC9") (pin "4") (pinfunction "OE_4") (pintype "input"))
      (node (ref "MOS7") (pin "1") (pinfunction "G_1") (pintype "bidirectional"))
      (node (ref "RN4") (pin "7") (pinfunction "2_7") (pintype "passive"))
    )
    (net (code "75") (name "/EN7R") (class "Default")
      (node (ref "RN4") (pin "2") (pinfunction "1_2") (pintype "passive"))
      (node (ref "SHIFT2") (pin "6") (pinfunction "QG_6") (pintype "tri_state"))
    )
    (net (code "76") (name "/EN8") (class "Default")
      (node (ref "IC9") (pin "10") (pinfunction "OE_10") (pintype "input"))
      (node (ref "IC9") (pin "13") (pinfunction "OE_13") (pintype "input"))
      (node (ref "MOS8") (pin "1") (pinfunction "G_1") (pintype "bidirectional"))
      (node (ref "RN4") (pin "8") (pinfunction "2_8") (pintype "passive"))
    )
    (net (code "77") (name "/EN8R") (class "Default")
      (node (ref "RN4") (pin "1") (pinfunction "1_1") (pintype "passive"))
      (node (ref "SHIFT2") (pin "7") (pinfunction "QH_7") (pintype "tri_state"))
    )
    (net (code "78") (name "/ENCLK") (class "Default")
      (node (ref "SHIFT2") (pin "11") (pinfunction "SCK_11") (pintype "input"))
      (node (ref "TEENSY_3.6") (pin "17/A3") (pinfunction "17/A3/PWM_17/A3") (pintype "bidirectional"))
    )
    (net (code "79") (name "/ENDATA") (class "Default")
      (node (ref "SHIFT2") (pin "14") (pinfunction "SER_14") (pintype "input"))
      (node (ref "TEENSY_3.6") (pin "19/A5") (pinfunction "19/A5/SCL0_19/A5") (pintype "bidirectional"))
    )
    (net (code "80") (name "/ENLATCH") (class "Default")
      (node (ref "SHIFT2") (pin "12") (pinfunction "RCK_12") (pintype "input"))
      (node (ref "TEENSY_3.6") (pin "18/A4") (pinfunction "18/A4/SDA0_18/A4") (pintype "bidirectional"))
    )
    (net (code "81") (name "/LATCHCLK") (class "Default")
      (node (ref "R1") (pin "2") (pinfunction "2_2") (pintype "passive"))
      (node (ref "SHIFT1") (pin "12") (pinfunction "RCK_12") (pintype "input"))
    )
    (net (code "82") (name "/LEDCLK") (class "Default")
      (node (ref "CLK-CLK") (pin "2") (pinfunction "A1_2") (pintype "bidirectional"))
      (node (ref "CLK-CLK") (pin "3") (pinfunction "A2_3") (pintype "bidirectional"))
      (node (ref "CLK-CLK") (pin "4") (pinfunction "A3_4") (pintype "bidirectional"))
      (node (ref "CLK-CLK") (pin "5") (pinfunction "A4_5") (pintype "bidirectional"))
      (node (ref "CLK-CLK") (pin "6") (pinfunction "A5_6") (pintype "bidirectional"))
      (node (ref "CLK-CLK") (pin "7") (pinfunction "A6_7") (pintype "bidirectional"))
      (node (ref "CLK-CLK") (pin "8") (pinfunction "A7_8") (pintype "bidirectional"))
      (node (ref "CLK-CLK") (pin "9") (pinfunction "A8_9") (pintype "bidirectional"))
      (node (ref "CLK-DATA") (pin "2") (pinfunction "A1_2") (pintype "bidirectional"))
      (node (ref "CLK-DATA") (pin "3") (pinfunction "A2_3") (pintype "bidirectional"))
      (node (ref "CLK-DATA") (pin "4") (pinfunction "A3_4") (pintype "bidirectional"))
      (node (ref "CLK-DATA") (pin "5") (pinfunction "A4_5") (pintype "bidirectional"))
      (node (ref "CLK-DATA") (pin "6") (pinfunction "A5_6") (pintype "bidirectional"))
      (node (ref "CLK-DATA") (pin "7") (pinfunction "A6_7") (pintype "bidirectional"))
      (node (ref "CLK-DATA") (pin "8") (pinfunction "A7_8") (pintype "bidirectional"))
      (node (ref "CLK-DATA") (pin "9") (pinfunction "A8_9") (pintype "bidirectional"))
      (node (ref "NAND") (pin "12") (pinfunction "I0_12") (pintype "input"))
      (node (ref "NAND") (pin "13") (pinfunction "I1_13") (pintype "input"))
      (node (ref "R3") (pin "1") (pinfunction "1_1") (pintype "passive"))
    )
    (net (code "83") (name "/MISO0") (class "Default")
      (node (ref "TEENSY_3.6") (pin "12") (pinfunction "12/MISO0_12") (pintype "bidirectional"))
      (node (ref "WIZNET820IO") (pin "J2.6") (pinfunction "MISO_J2.6") (pintype "output"))
    )
    (net (code "84") (name "/MOSI0") (class "Default")
      (node (ref "TEENSY_3.6") (pin "11") (pinfunction "11/MOSI0_11") (pintype "bidirectional"))
      (node (ref "WIZNET820IO") (pin "J1.3") (pinfunction "MOSI_J1.3") (pintype "input"))
    )
    (net (code "85") (name "/OCTO1") (class "Default")
      (node (ref "OCTOCLK") (pin "9") (pinfunction "A8_9") (pintype "bidirectional"))
      (node (ref "OCTODATA") (pin "2") (pinfunction "A1_2") (pintype "bidirectional"))
      (node (ref "TEENSY_3.6") (pin "2") (pinfunction "2/PWM_2") (pintype "bidirectional"))
    )
    (net (code "86") (name "/OCTO2") (class "Default")
      (node (ref "OCTOCLK") (pin "8") (pinfunction "A7_8") (pintype "bidirectional"))
      (node (ref "OCTODATA") (pin "3") (pinfunction "A2_3") (pintype "bidirectional"))
      (node (ref "TEENSY_3.6") (pin "14/A0") (pinfunction "14/A0/PWM_14/A0") (pintype "bidirectional"))
    )
    (net (code "87") (name "/OCTO3") (class "Default")
      (node (ref "OCTOCLK") (pin "7") (pinfunction "A6_7") (pintype "bidirectional"))
      (node (ref "OCTODATA") (pin "4") (pinfunction "A3_4") (pintype "bidirectional"))
      (node (ref "TEENSY_3.6") (pin "7") (pinfunction "7/RX3/PWM_7") (pintype "bidirectional"))
    )
    (net (code "88") (name "/OCTO4") (class "Default")
      (node (ref "OCTOCLK") (pin "6") (pinfunction "A5_6") (pintype "bidirectional"))
      (node (ref "OCTODATA") (pin "5") (pinfunction "A4_5") (pintype "bidirectional"))
      (node (ref "TEENSY_3.6") (pin "8") (pinfunction "8/TX3/PWM_8") (pintype "bidirectional"))
    )
    (net (code "89") (name "/OCTO5{slash}RST") (class "Default")
      (node (ref "IC6") (pin "2") (pinfunction "CLR_2") (pintype "input"))
      (node (ref "OCTOCLK") (pin "5") (pinfunction "A4_5") (pintype "bidirectional"))
      (node (ref "OCTODATA") (pin "6") (pinfunction "A5_6") (pintype "bidirectional"))
      (node (ref "TEENSY_3.6") (pin "6") (pinfunction "6/PWM_6") (pintype "bidirectional"))
    )
    (net (code "90") (name "/OCTO6{slash}SCK1") (class "Default")
      (node (ref "IC6") (pin "1") (pinfunction "A_1") (pintype "input"))
      (node (ref "OCTOCLK") (pin "4") (pinfunction "A3_4") (pintype "bidirectional"))
      (node (ref "OCTODATA") (pin "7") (pinfunction "A6_7") (pintype "bidirectional"))
      (node (ref "R11") (pin "1") (pinfunction "1_1") (pintype "passive"))
      (node (ref "SHIFT1") (pin "11") (pinfunction "SCK_11") (pintype "input"))
    )
    (net (code "91") (name "/OCTO7{slash}MOSI1") (class "Default")
      (node (ref "OCTOCLK") (pin "3") (pinfunction "A2_3") (pintype "bidirectional"))
      (node (ref "OCTODATA") (pin "8") (pinfunction "A7_8") (pintype "bidirectional"))
      (node (ref "R26") (pin "2") (pinfunction "2_2") (pintype "passive"))
      (node (ref "SHIFT1") (pin "14") (pinfunction "SER_14") (pintype "input"))
    )
    (net (code "92") (name "/OCTO8") (class "Default")
      (node (ref "OCTOCLK") (pin "2") (pinfunction "A1_2") (pintype "bidirectional"))
      (node (ref "OCTODATA") (pin "9") (pinfunction "A8_9") (pintype "bidirectional"))
      (node (ref "TEENSY_3.6") (pin "5") (pinfunction "5/PWM_5") (pintype "bidirectional"))
    )
    (net (code "93") (name "/OCTOEN") (class "Default")
      (node (ref "NAND") (pin "1") (pinfunction "I0_1") (pintype "input"))
      (node (ref "NAND") (pin "5") (pinfunction "I1_5") (pintype "input"))
      (node (ref "OCTOCLK") (pin "19") (pinfunction "G_19") (pintype "input"))
      (node (ref "OCTODATA") (pin "19") (pinfunction "G_19") (pintype "input"))
      (node (ref "TEENSY_3.6") (pin "23/A9") (pinfunction "23/A9/PWM_23/A9") (pintype "bidirectional"))
    )
    (net (code "94") (name "/RESET") (class "Default")
      (node (ref "TEENSY_3.6") (pin "9") (pinfunction "9/RX2/PWM_9") (pintype "bidirectional"))
      (node (ref "WIZNET820IO") (pin "J2.5") (pinfunction "/RESET_J2.5") (pintype "input"))
    )
    (net (code "95") (name "/SCK0") (class "Default")
      (node (ref "TEENSY_3.6") (pin "13") (pinfunction "13/SCK0/LED_13") (pintype "bidirectional"))
      (node (ref "WIZNET820IO") (pin "J1.4") (pinfunction "SCLK_J1.4") (pintype "input"))
    )
    (net (code "96") (name "/SHIFT1RI") (class "Default")
      (node (ref "RN1") (pin "1") (pinfunction "1_1") (pintype "passive"))
      (node (ref "SHIFT1") (pin "15") (pinfunction "QA_15") (pintype "tri_state"))
    )
    (net (code "97") (name "/SHIFT1RO") (class "Default")
      (node (ref "DATA-CLK") (pin "9") (pinfunction "A8_9") (pintype "bidirectional"))
      (node (ref "DATA-DATA") (pin "2") (pinfunction "A1_2") (pintype "bidirectional"))
      (node (ref "RN1") (pin "8") (pinfunction "2_8") (pintype "passive"))
    )
    (net (code "98") (name "/SHIFT2RI") (class "Default")
      (node (ref "RN1") (pin "2") (pinfunction "1_2") (pintype "passive"))
      (node (ref "SHIFT1") (pin "1") (pinfunction "QB_1") (pintype "tri_state"))
    )
    (net (code "99") (name "/SHIFT2RO") (class "Default")
      (node (ref "DATA-CLK") (pin "8") (pinfunction "A7_8") (pintype "bidirectional"))
      (node (ref "DATA-DATA") (pin "3") (pinfunction "A2_3") (pintype "bidirectional"))
      (node (ref "RN1") (pin "7") (pinfunction "2_7") (pintype "passive"))
    )
    (net (code "100") (name "/SHIFT3RI") (class "Default")
      (node (ref "RN1") (pin "3") (pinfunction "1_3") (pintype "passive"))
      (node (ref "SHIFT1") (pin "2") (pinfunction "QC_2") (pintype "tri_state"))
    )
    (net (code "101") (name "/SHIFT3RO") (class "Default")
      (node (ref "DATA-CLK") (pin "7") (pinfunction "A6_7") (pintype "bidirectional"))
      (node (ref "DATA-DATA") (pin "4") (pinfunction "A3_4") (pintype "bidirectional"))
      (node (ref "RN1") (pin "6") (pinfunction "2_6") (pintype "passive"))
    )
    (net (code "102") (name "/SHIFT4RI") (class "Default")
      (node (ref "RN1") (pin "4") (pinfunction "1_4") (pintype "passive"))
      (node (ref "SHIFT1") (pin "3") (pinfunction "QD_3") (pintype "tri_state"))
    )
    (net (code "103") (name "/SHIFT4RO") (class "Default")
      (node (ref "DATA-CLK") (pin "6") (pinfunction "A5_6") (pintype "bidirectional"))
      (node (ref "DATA-DATA") (pin "5") (pinfunction "A4_5") (pintype "bidirectional"))
      (node (ref "RN1") (pin "5") (pinfunction "2_5") (pintype "passive"))
    )
    (net (code "104") (name "/SHIFT5RI") (class "Default")
      (node (ref "RN2") (pin "1") (pinfunction "1_1") (pintype "passive"))
      (node (ref "SHIFT1") (pin "4") (pinfunction "QE_4") (pintype "tri_state"))
    )
    (net (code "105") (name "/SHIFT5RO") (class "Default")
      (node (ref "DATA-CLK") (pin "5") (pinfunction "A4_5") (pintype "bidirectional"))
      (node (ref "DATA-DATA") (pin "6") (pinfunction "A5_6") (pintype "bidirectional"))
      (node (ref "RN2") (pin "8") (pinfunction "2_8") (pintype "passive"))
    )
    (net (code "106") (name "/SHIFT6RI") (class "Default")
      (node (ref "RN2") (pin "2") (pinfunction "1_2") (pintype "passive"))
      (node (ref "SHIFT1") (pin "5") (pinfunction "QF_5") (pintype "tri_state"))
    )
    (net (code "107") (name "/SHIFT6RO") (class "Default")
      (node (ref "DATA-CLK") (pin "4") (pinfunction "A3_4") (pintype "bidirectional"))
      (node (ref "DATA-DATA") (pin "7") (pinfunction "A6_7") (pintype "bidirectional"))
      (node (ref "RN2") (pin "7") (pinfunction "2_7") (pintype "passive"))
    )
    (net (code "108") (name "/SHIFT7RI") (class "Default")
      (node (ref "RN2") (pin "3") (pinfunction "1_3") (pintype "passive"))
      (node (ref "SHIFT1") (pin "6") (pinfunction "QG_6") (pintype "tri_state"))
    )
    (net (code "109") (name "/SHIFT7RO") (class "Default")
      (node (ref "DATA-CLK") (pin "3") (pinfunction "A2_3") (pintype "bidirectional"))
      (node (ref "DATA-DATA") (pin "8") (pinfunction "A7_8") (pintype "bidirectional"))
      (node (ref "RN2") (pin "6") (pinfunction "2_6") (pintype "passive"))
    )
    (net (code "110") (name "/SHIFT8RI") (class "Default")
      (node (ref "RN2") (pin "4") (pinfunction "1_4") (pintype "passive"))
      (node (ref "SHIFT1") (pin "7") (pinfunction "QH_7") (pintype "tri_state"))
    )
    (net (code "111") (name "/SHIFT8RO") (class "Default")
      (node (ref "DATA-CLK") (pin "2") (pinfunction "A1_2") (pintype "bidirectional"))
      (node (ref "DATA-DATA") (pin "9") (pinfunction "A8_9") (pintype "bidirectional"))
      (node (ref "RN2") (pin "5") (pinfunction "2_5") (pintype "passive"))
    )
    (net (code "112") (name "/SOURCE1") (class "Default")
      (node (ref "F1") (pin "1") (pinfunction "1_1") (pintype "passive"))
      (node (ref "MOS1") (pin "2") (pinfunction "D_2") (pintype "bidirectional"))
    )
    (net (code "113") (name "/SOURCE2") (class "Default")
      (node (ref "F2") (pin "1") (pinfunction "1_1") (pintype "passive"))
      (node (ref "MOS2") (pin "2") (pinfunction "D_2") (pintype "bidirectional"))
    )
    (net (code "114") (name "/SOURCE3") (class "Default")
      (node (ref "F3") (pin "1") (pinfunction "1_1") (pintype "passive"))
      (node (ref "MOS3") (pin "2") (pinfunction "D_2") (pintype "bidirectional"))
    )
    (net (code "115") (name "/SOURCE4") (class "Default")
      (node (ref "F4") (pin "1") (pinfunction "1_1") (pintype "passive"))
      (node (ref "MOS4") (pin "2") (pinfunction "D_2") (pintype "bidirectional"))
    )
    (net (code "116") (name "/SOURCE5") (class "Default")
      (node (ref "F5") (pin "1") (pinfunction "1_1") (pintype "passive"))
      (node (ref "MOS5") (pin "2") (pinfunction "D_2") (pintype "bidirectional"))
    )
    (net (code "117") (name "/SOURCE6") (class "Default")
      (node (ref "F6") (pin "1") (pinfunction "1_1") (pintype "passive"))
      (node (ref "MOS6") (pin "2") (pinfunction "D_2") (pintype "bidirectional"))
    )
    (net (code "118") (name "/SOURCE7") (class "Default")
      (node (ref "F7") (pin "1") (pinfunction "1_1") (pintype "passive"))
      (node (ref "MOS7") (pin "2") (pinfunction "D_2") (pintype "bidirectional"))
    )
    (net (code "119") (name "/SOURCE8") (class "Default")
      (node (ref "F8") (pin "1") (pinfunction "1_1") (pintype "passive"))
      (node (ref "MOS8") (pin "2") (pinfunction "D_2") (pintype "bidirectional"))
    )
    (net (code "120") (name "/SPI1EN") (class "Default")
      (node (ref "CLK-CLK") (pin "19") (pinfunction "G_19") (pintype "input"))
      (node (ref "DATA-DATA") (pin "19") (pinfunction "G_19") (pintype "input"))
      (node (ref "NAND") (pin "3") (pinfunction "O_3") (pintype "output"))
      (node (ref "NAND") (pin "4") (pinfunction "I0_4") (pintype "input"))
    )
    (net (code "121") (name "/SPI2EN") (class "Default")
      (node (ref "CLK-DATA") (pin "19") (pinfunction "G_19") (pintype "input"))
      (node (ref "DATA-CLK") (pin "19") (pinfunction "G_19") (pintype "input"))
      (node (ref "NAND") (pin "6") (pinfunction "O_6") (pintype "output"))
    )
    (net (code "122") (name "/SPI_SW") (class "Default")
      (node (ref "NAND") (pin "2") (pinfunction "I1_2") (pintype "input"))
      (node (ref "TEENSY_3.6") (pin "22/A8") (pinfunction "22/A8/PWM_22/A8") (pintype "bidirectional"))
    )
    (net (code "123") (name "/SS") (class "Default")
      (node (ref "TEENSY_3.6") (pin "10") (pinfunction "10/TX2/PWM_10") (pintype "bidirectional"))
      (node (ref "WIZNET820IO") (pin "J1.5") (pinfunction "/SS_J1.5") (pintype "input"))
    )
    (net (code "124") (name "GND") (class "Default")
      (node (ref "C1") (pin "2") (pinfunction "2_2") (pintype "passive"))
      (node (ref "C10") (pin "2") (pinfunction "2_2") (pintype "passive"))
      (node (ref "C11") (pin "2") (pinfunction "2_2") (pintype "passive"))
      (node (ref "C12") (pin "2") (pinfunction "2_2") (pintype "passive"))
      (node (ref "C2") (pin "2") (pinfunction "2_2") (pintype "passive"))
      (node (ref "C3") (pin "2") (pinfunction "2_2") (pintype "passive"))
      (node (ref "C4") (pin "2") (pinfunction "2_2") (pintype "passive"))
      (node (ref "C5") (pin "2") (pinfunction "2_2") (pintype "passive"))
      (node (ref "C6") (pin "2") (pinfunction "2_2") (pintype "passive"))
      (node (ref "C7") (pin "2") (pinfunction "2_2") (pintype "passive"))
      (node (ref "C8") (pin "2") (pinfunction "2_2") (pintype "passive"))
      (node (ref "C9") (pin "2") (pinfunction "2_2") (pintype "passive"))
      (node (ref "CLK-CLK") (pin "10") (pinfunction "GND_10") (pintype "power_in"))
      (node (ref "CLK-DATA") (pin "10") (pinfunction "GND_10") (pintype "power_in"))
      (node (ref "DATA-CLK") (pin "10") (pinfunction "GND_10") (pintype "power_in"))
      (node (ref "DATA-DATA") (pin "10") (pinfunction "GND_10") (pintype "power_in"))
      (node (ref "F1") (pin "3") (pinfunction "2_3") (pintype "passive"))
      (node (ref "F1") (pin "4") (pinfunction "2_4") (pintype "passive"))
      (node (ref "F2") (pin "3") (pinfunction "2_3") (pintype "passive"))
      (node (ref "F2") (pin "4") (pinfunction "2_4") (pintype "passive"))
      (node (ref "F3") (pin "3") (pinfunction "2_3") (pintype "passive"))
      (node (ref "F3") (pin "4") (pinfunction "2_4") (pintype "passive"))
      (node (ref "F4") (pin "3") (pinfunction "2_3") (pintype "passive"))
      (node (ref "F4") (pin "4") (pinfunction "2_4") (pintype "passive"))
      (node (ref "F5") (pin "3") (pinfunction "2_3") (pintype "passive"))
      (node (ref "F5") (pin "4") (pinfunction "2_4") (pintype "passive"))
      (node (ref "F6") (pin "3") (pinfunction "2_3") (pintype "passive"))
      (node (ref "F6") (pin "4") (pinfunction "2_4") (pintype "passive"))
      (node (ref "F7") (pin "3") (pinfunction "2_3") (pintype "passive"))
      (node (ref "F7") (pin "4") (pinfunction "2_4") (pintype "passive"))
      (node (ref "F8") (pin "3") (pinfunction "2_3") (pintype "passive"))
      (node (ref "F8") (pin "4") (pinfunction "2_4") (pintype "passive"))
      (node (ref "H1") (pin "1") (pinfunction "1_1") (pintype "bidirectional"))
      (node (ref "H1") (pin "4") (pinfunction "4_4") (pintype "bidirectional"))
      (node (ref "H2") (pin "3") (pinfunction "3_3") (pintype "bidirectional"))
      (node (ref "H3") (pin "2") (pinfunction "2_2") (pintype "bidirectional"))
      (node (ref "IC6") (pin "7") (pinfunction "GND_7") (pintype "power_in"))
      (node (ref "J5") (pin "BLACK") (pinfunction "GND_BLACK") (pintype "power_in"))
      (node (ref "JP1") (pin "10") (pinfunction "10_10") (pintype "bidirectional"))
      (node (ref "JP2") (pin "10") (pinfunction "10_10") (pintype "bidirectional"))
      (node (ref "NAND") (pin "7") (pinfunction "GND_7") (pintype "power_in"))
      (node (ref "OCTOCLK") (pin "10") (pinfunction "GND_10") (pintype "power_in"))
      (node (ref "OCTODATA") (pin "10") (pinfunction "GND_10") (pintype "power_in"))
      (node (ref "SHIFT1") (pin "13") (pinfunction "G_13") (pintype "input"))
      (node (ref "SHIFT1") (pin "8") (pinfunction "GND_8") (pintype "power_in"))
      (node (ref "SHIFT2") (pin "13") (pinfunction "G_13") (pintype "input"))
      (node (ref "SHIFT2") (pin "8") (pinfunction "GND_8") (pintype "power_in"))
      (node (ref "TEENSY_3.6") (pin "GND") (pinfunction "GND_GND") (pintype "power_in"))
      (node (ref "TEENSY_3.6") (pin "GND1") (pinfunction "GND_GND1") (pintype "power_in"))
      (node (ref "U$1") (pin "2") (pinfunction "GND_2") (pintype "input"))
      (node (ref "U$1") (pin "4") (pinfunction "GND_4") (pintype "input"))
      (node (ref "WIZNET820IO") (pin "J1.1") (pinfunction "GND1_J1.1") (pintype "power_in"))
      (node (ref "WIZNET820IO") (pin "J1.2") (pinfunction "GND2_J1.2") (pintype "power_in"))
      (node (ref "WIZNET820IO") (pin "J2.1") (pinfunction "GND3_J2.1") (pintype "power_in"))
      (node (ref "WIZNET820IO") (pin "J2.4") (pinfunction "PWDN_J2.4") (pintype "input"))
    )
    (net (code "125") (name "Net-(IC5A-O)") (class "Default")
      (node (ref "IC5") (pin "3") (pinfunction "O_3") (pintype "output"))
      (node (ref "RN5") (pin "3") (pinfunction "1_3") (pintype "passive"))
    )
    (net (code "126") (name "Net-(IC5B-O)") (class "Default")
      (node (ref "IC5") (pin "6") (pinfunction "O_6") (pintype "output"))
      (node (ref "RN5") (pin "4") (pinfunction "1_4") (pintype "passive"))
    )
    (net (code "127") (name "Net-(IC5C-O)") (class "Default")
      (node (ref "IC5") (pin "8") (pinfunction "O_8") (pintype "output"))
      (node (ref "RN5") (pin "1") (pinfunction "1_1") (pintype "passive"))
    )
    (net (code "128") (name "Net-(IC5D-O)") (class "Default")
      (node (ref "IC5") (pin "11") (pinfunction "O_11") (pintype "output"))
      (node (ref "RN5") (pin "2") (pinfunction "1_2") (pintype "passive"))
    )
    (net (code "129") (name "Net-(IC6A-QC)") (class "Default")
      (node (ref "IC6") (pin "5") (pinfunction "QC_5") (pintype "output"))
      (node (ref "R3") (pin "2") (pinfunction "2_2") (pintype "passive"))
    )
    (net (code "130") (name "Net-(IC7A-O)") (class "Default")
      (node (ref "IC7") (pin "3") (pinfunction "O_3") (pintype "output"))
      (node (ref "RN6") (pin "3") (pinfunction "1_3") (pintype "passive"))
    )
    (net (code "131") (name "Net-(IC7B-O)") (class "Default")
      (node (ref "IC7") (pin "6") (pinfunction "O_6") (pintype "output"))
      (node (ref "RN6") (pin "4") (pinfunction "1_4") (pintype "passive"))
    )
    (net (code "132") (name "Net-(IC7C-O)") (class "Default")
      (node (ref "IC7") (pin "8") (pinfunction "O_8") (pintype "output"))
      (node (ref "RN6") (pin "1") (pinfunction "1_1") (pintype "passive"))
    )
    (net (code "133") (name "Net-(IC7D-O)") (class "Default")
      (node (ref "IC7") (pin "11") (pinfunction "O_11") (pintype "output"))
      (node (ref "RN6") (pin "2") (pinfunction "1_2") (pintype "passive"))
    )
    (net (code "134") (name "Net-(IC8A-O)") (class "Default")
      (node (ref "IC8") (pin "3") (pinfunction "O_3") (pintype "output"))
      (node (ref "RN7") (pin "3") (pinfunction "1_3") (pintype "passive"))
    )
    (net (code "135") (name "Net-(IC8B-O)") (class "Default")
      (node (ref "IC8") (pin "6") (pinfunction "O_6") (pintype "output"))
      (node (ref "RN7") (pin "4") (pinfunction "1_4") (pintype "passive"))
    )
    (net (code "136") (name "Net-(IC8C-O)") (class "Default")
      (node (ref "IC8") (pin "8") (pinfunction "O_8") (pintype "output"))
      (node (ref "RN7") (pin "1") (pinfunction "1_1") (pintype "passive"))
    )
    (net (code "137") (name "Net-(IC8D-O)") (class "Default")
      (node (ref "IC8") (pin "11") (pinfunction "O_11") (pintype "output"))
      (node (ref "RN7") (pin "2") (pinfunction "1_2") (pintype "passive"))
    )
    (net (code "138") (name "Net-(IC9A-O)") (class "Default")
      (node (ref "IC9") (pin "3") (pinfunction "O_3") (pintype "output"))
      (node (ref "RN8") (pin "3") (pinfunction "1_3") (pintype "passive"))
    )
    (net (code "139") (name "Net-(IC9B-O)") (class "Default")
      (node (ref "IC9") (pin "6") (pinfunction "O_6") (pintype "output"))
      (node (ref "RN8") (pin "4") (pinfunction "1_4") (pintype "passive"))
    )
    (net (code "140") (name "Net-(IC9C-O)") (class "Default")
      (node (ref "IC9") (pin "8") (pinfunction "O_8") (pintype "output"))
      (node (ref "RN8") (pin "1") (pinfunction "1_1") (pintype "passive"))
    )
    (net (code "141") (name "Net-(IC9D-O)") (class "Default")
      (node (ref "IC9") (pin "11") (pinfunction "O_11") (pintype "output"))
      (node (ref "RN8") (pin "2") (pinfunction "1_2") (pintype "passive"))
    )
    (net (code "142") (name "Net-(NANDD-O)") (class "Default")
      (node (ref "NAND") (pin "11") (pinfunction "O_11") (pintype "output"))
      (node (ref "R1") (pin "1") (pinfunction "1_1") (pintype "passive"))
    )
    (net (code "143") (name "Net-(TEENSY_3.6-0{slash}RX1{slash}MOSI1)") (class "Default")
      (node (ref "H2") (pin "2") (pinfunction "2_2") (pintype "bidirectional"))
      (node (ref "TEENSY_3.6") (pin "0") (pinfunction "0/RX1/MOSI1_0") (pintype "bidirectional"))
    )
    (net (code "144") (name "Net-(TEENSY_3.6-1{slash}TX1{slash}MISO1)") (class "Default")
      (node (ref "H2") (pin "1") (pinfunction "1_1") (pintype "bidirectional"))
      (node (ref "TEENSY_3.6") (pin "1") (pinfunction "1/TX1/MISO1_1") (pintype "bidirectional"))
    )
    (net (code "145") (name "Net-(TEENSY_3.6-A21{slash}DAC0)") (class "Default")
      (node (ref "H1") (pin "2") (pinfunction "2_2") (pintype "bidirectional"))
      (node (ref "TEENSY_3.6") (pin "A21") (pinfunction "A21/DAC0_A21") (pintype "bidirectional"))
    )
    (net (code "146") (name "Net-(TEENSY_3.6-A22{slash}DAC1)") (class "Default")
      (node (ref "H1") (pin "3") (pinfunction "3_3") (pintype "bidirectional"))
      (node (ref "TEENSY_3.6") (pin "A22") (pinfunction "A22/DAC1_A22") (pintype "bidirectional"))
    )
    (net (code "147") (name "VCC") (class "Default")
      (node (ref "C1") (pin "1") (pinfunction "1_1") (pintype "passive"))
      (node (ref "C10") (pin "1") (pinfunction "1_1") (pintype "passive"))
      (node (ref "C11") (pin "1") (pinfunction "1_1") (pintype "passive"))
      (node (ref "C12") (pin "1") (pinfunction "1_1") (pintype "passive"))
      (node (ref "C2") (pin "1") (pinfunction "1_1") (pintype "passive"))
      (node (ref "C4") (pin "1") (pinfunction "1_1") (pintype "passive"))
      (node (ref "C5") (pin "1") (pinfunction "1_1") (pintype "passive"))
      (node (ref "C6") (pin "1") (pinfunction "1_1") (pintype "passive"))
      (node (ref "C7") (pin "1") (pinfunction "1_1") (pintype "passive"))
      (node (ref "C8") (pin "1") (pinfunction "1_1") (pintype "passive"))
      (node (ref "C9") (pin "1") (pinfunction "1_1") (pintype "passive"))
      (node (ref "CLK-CLK") (pin "1") (pinfunction "DIR_1") (pintype "input"))
      (node (ref "CLK-CLK") (pin "20") (pinfunction "VCC_20") (pintype "power_in"))
      (node (ref "CLK-DATA") (pin "1") (pinfunction "DIR_1") (pintype "input"))
      (node (ref "CLK-DATA") (pin "20") (pinfunction "VCC_20") (pintype "power_in"))
      (node (ref "DATA-CLK") (pin "1") (pinfunction "DIR_1") (pintype "input"))
      (node (ref "DATA-CLK") (pin "20") (pinfunction "VCC_20") (pintype "power_in"))
      (node (ref "DATA-DATA") (pin "1") (pinfunction "DIR_1") (pintype "input"))
      (node (ref "DATA-DATA") (pin "20") (pinfunction "VCC_20") (pintype "power_in"))
      (node (ref "H3") (pin "1") (pinfunction "1_1") (pintype "bidirectional"))
      (node (ref "IC6") (pin "14") (pinfunction "VCC_14") (pintype "power_in"))
      (node (ref "J1") (pin "1") (pinfunction "1_1") (pintype "passive"))
      (node (ref "J1") (pin "2") (pinfunction "2_2") (pintype "passive"))
      (node (ref "J2") (pin "1") (pinfunction "1_1") (pintype "passive"))
      (node (ref "J2") (pin "2") (pinfunction "2_2") (pintype "passive"))
      (node (ref "J3") (pin "1") (pinfunction "1_1") (pintype "passive"))
      (node (ref "J3") (pin "2") (pinfunction "2_2") (pintype "passive"))
      (node (ref "J4") (pin "1") (pinfunction "1_1") (pintype "passive"))
      (node (ref "J4") (pin "2") (pinfunction "2_2") (pintype "passive"))
      (node (ref "J5") (pin "RED") (pinfunction "V+_RED") (pintype "power_in"))
      (node (ref "LED1") (pin "1") (pinfunction "1_1") (pintype "passive"))
      (node (ref "LED2") (pin "1") (pinfunction "1_1") (pintype "passive"))
      (node (ref "LED3") (pin "1") (pinfunction "1_1") (pintype "passive"))
      (node (ref "LED4") (pin "1") (pinfunction "1_1") (pintype "passive"))
      (node (ref "LED5") (pin "1") (pinfunction "1_1") (pintype "passive"))
      (node (ref "LED6") (pin "1") (pinfunction "1_1") (pintype "passive"))
      (node (ref "LED7") (pin "1") (pinfunction "1_1") (pintype "passive"))
      (node (ref "LED8") (pin "1") (pinfunction "1_1") (pintype "passive"))
      (node (ref "NAND") (pin "14") (pinfunction "VCC_14") (pintype "power_in"))
      (node (ref "OCTOCLK") (pin "1") (pinfunction "DIR_1") (pintype "input"))
      (node (ref "OCTOCLK") (pin "20") (pinfunction "VCC_20") (pintype "power_in"))
      (node (ref "OCTODATA") (pin "1") (pinfunction "DIR_1") (pintype "input"))
      (node (ref "OCTODATA") (pin "20") (pinfunction "VCC_20") (pintype "power_in"))
      (node (ref "SHIFT1") (pin "10") (pinfunction "SCL_10") (pintype "input"))
      (node (ref "SHIFT1") (pin "16") (pinfunction "VCC_16") (pintype "power_in"))
      (node (ref "SHIFT2") (pin "10") (pinfunction "SCL_10") (pintype "input"))
      (node (ref "SHIFT2") (pin "16") (pinfunction "VCC_16") (pintype "power_in"))
      (node (ref "TEENSY_3.6") (pin "VIN") (pinfunction "VIN_VIN") (pintype "power_in"))
      (node (ref "U$1") (pin "1") (pinfunction "IN_1") (pintype "input"))
    )
    (net (code "148") (name "unconnected-(IC6A-QA-Pad3)") (class "Default")
      (node (ref "IC6") (pin "3") (pinfunction "QA_3") (pintype "output"))
    )
    (net (code "149") (name "unconnected-(IC6A-QB-Pad4)") (class "Default")
      (node (ref "IC6") (pin "4") (pinfunction "QB_4") (pintype "output"))
    )
    (net (code "150") (name "unconnected-(IC6A-QD-Pad6)") (class "Default")
      (node (ref "IC6") (pin "6") (pinfunction "QD_6") (pintype "output"))
    )
    (net (code "151") (name "unconnected-(IC6B-A-Pad13)") (class "Default")
      (node (ref "IC6") (pin "13") (pinfunction "A_13") (pintype "input"))
    )
    (net (code "152") (name "unconnected-(IC6B-CLR-Pad12)") (class "Default")
      (node (ref "IC6") (pin "12") (pinfunction "CLR_12") (pintype "input"))
    )
    (net (code "153") (name "unconnected-(IC6B-QA-Pad11)") (class "Default")
      (node (ref "IC6") (pin "11") (pinfunction "QA_11") (pintype "output"))
    )
    (net (code "154") (name "unconnected-(IC6B-QB-Pad10)") (class "Default")
      (node (ref "IC6") (pin "10") (pinfunction "QB_10") (pintype "output"))
    )
    (net (code "155") (name "unconnected-(IC6B-QC-Pad9)") (class "Default")
      (node (ref "IC6") (pin "9") (pinfunction "QC_9") (pintype "output"))
    )
    (net (code "156") (name "unconnected-(IC6B-QD-Pad8)") (class "Default")
      (node (ref "IC6") (pin "8") (pinfunction "QD_8") (pintype "output"))
    )
    (net (code "157") (name "unconnected-(NANDC-I0-Pad9)") (class "Default")
      (node (ref "NAND") (pin "9") (pinfunction "I0_9") (pintype "input"))
    )
    (net (code "158") (name "unconnected-(NANDC-I1-Pad10)") (class "Default")
      (node (ref "NAND") (pin "10") (pinfunction "I1_10") (pintype "input"))
    )
    (net (code "159") (name "unconnected-(NANDC-O-Pad8)") (class "Default")
      (node (ref "NAND") (pin "8") (pinfunction "O_8") (pintype "output"))
    )
    (net (code "160") (name "unconnected-(SHIFT1-QH*-Pad9)") (class "Default")
      (node (ref "SHIFT1") (pin "9") (pinfunction "QH*_9") (pintype "tri_state"))
    )
    (net (code "161") (name "unconnected-(SHIFT2-QH*-Pad9)") (class "Default")
      (node (ref "SHIFT2") (pin "9") (pinfunction "QH*_9") (pintype "tri_state"))
    )
    (net (code "162") (name "unconnected-(TEENSY_3.6-3{slash}CAN0-TX{slash}SCL2{slash}PWM-Pad3)") (class "Default")
      (node (ref "TEENSY_3.6") (pin "3") (pinfunction "3/CAN0-TX/SCL2/PWM_3") (pintype "bidirectional"))
    )
    (net (code "163") (name "unconnected-(TEENSY_3.6-4{slash}CAN0-RX{slash}SDA2{slash}PWM-Pad4)") (class "Default")
      (node (ref "TEENSY_3.6") (pin "4") (pinfunction "4/CAN0-RX/SDA2/PWM_4") (pintype "bidirectional"))
    )
    (net (code "164") (name "unconnected-(TEENSY_3.6-Pad15{slash}A1)") (class "Default")
      (node (ref "TEENSY_3.6") (pin "15/A1") (pinfunction "15/A1_15/A1") (pintype "bidirectional"))
    )
    (net (code "165") (name "unconnected-(TEENSY_3.6-Pad16{slash}A2)") (class "Default")
      (node (ref "TEENSY_3.6") (pin "16/A2") (pinfunction "16/A2_16/A2") (pintype "bidirectional"))
    )
    (net (code "166") (name "unconnected-(WIZNET820IO-{slash}INT-PadJ1.6)") (class "Default")
      (node (ref "WIZNET820IO") (pin "J1.6") (pinfunction "/INT_J1.6") (pintype "output"))
    )
  )
)
